# analog.net
KiCad netlist of a schematic drawn in Altium Designer
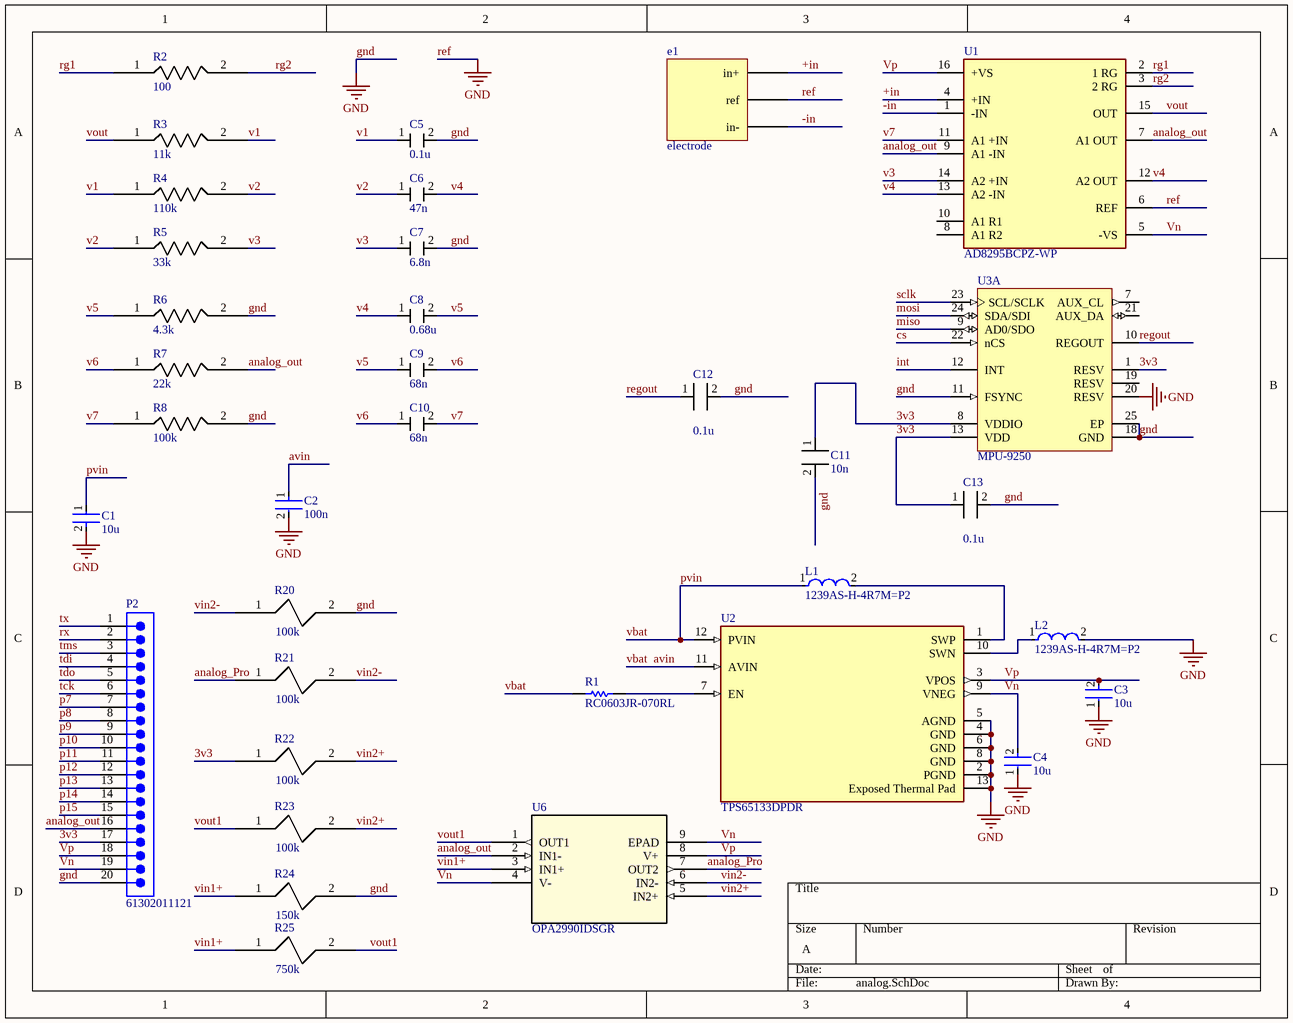
[diagram p0: analog.SchDoc]

(export (version "E")
  (design (tool "Eeschema 10.0.6"))
  (components
    (comp (ref "C1")
      (value "10u")
      (footprint "FP-C1608-080-0_1-MFG")
      (description "C19702")
      (fields (field (name "VOLTAGE") "10V") (field (name "TOLERANCE") "10%"))
      (libsource (lib "Altium Content Vault") (part "236180d848d6139a670b325ea6854c9"))
    )
    (comp (ref "C2")
      (value "100n")
      (footprint "FP-CGA3E-0_3-0_1-IPC_A")
      (description "C14663")
      (fields (field (name "TOLERANCE") "10%") (field (name "VOLTAGE") "50V"))
      (libsource (lib "Altium Content Vault") (part "b4654b650e69147ec39a6b967a45e02"))
    )
    (comp (ref "C3")
      (value "10u")
      (footprint "FP-C1608-080-0_1-MFG")
      (description "C6119842")
      (fields (field (name "VOLTAGE") "10V") (field (name "TOLERANCE") "10%"))
      (libsource (lib "Altium Content Vault") (part "236180d848d6139a670b325ea6854c9"))
    )
    (comp (ref "C4")
      (value "10u")
      (footprint "FP-C1608-080-0_1-MFG")
      (description "C6119842")
      (fields (field (name "VOLTAGE") "10V") (field (name "TOLERANCE") "10%"))
      (libsource (lib "Altium Content Vault") (part "236180d848d6139a670b325ea6854c9"))
    )
    (comp (ref "C5")
      (value "genCap")
      (footprint "GeneralCap")
      (description "C14663")
      (fields (field (name "C") "0.1u"))
      (libsource (lib "") (part "genCap_1"))
    )
    (comp (ref "C6")
      (value "genCap")
      (footprint "GeneralCap")
      (description "C107093")
      (fields (field (name "C") "47n"))
      (libsource (lib "") (part "genCap_1"))
    )
    (comp (ref "C7")
      (value "genCap")
      (footprint "GeneralCap")
      (description "C162241")
      (fields (field (name "C") "6.8n"))
      (libsource (lib "") (part "genCap_1"))
    )
    (comp (ref "C8")
      (value "genCap")
      (footprint "GeneralCap")
      (description "C694504")
      (fields (field (name "C") "0.68u"))
      (libsource (lib "") (part "genCap_1"))
    )
    (comp (ref "C9")
      (value "genCap")
      (footprint "GeneralCap")
      (description "C107098")
      (fields (field (name "C") "68n"))
      (libsource (lib "") (part "genCap_1"))
    )
    (comp (ref "C10")
      (value "genCap")
      (footprint "GeneralCap")
      (description "C107098")
      (fields (field (name "C") "68n"))
      (libsource (lib "") (part "genCap_1"))
    )
    (comp (ref "C11")
      (value "genCap")
      (footprint "GeneralCap")
      (description "C100042")
      (fields (field (name "C") "10n"))
      (libsource (lib "seniorDesign") (part "genCap"))
    )
    (comp (ref "C12")
      (value "genCap")
      (footprint "GeneralCap")
      (description "C14663")
      (fields (field (name "C") "0.1u"))
      (libsource (lib "seniorDesign") (part "genCap"))
    )
    (comp (ref "C13")
      (value "genCap")
      (footprint "GeneralCap")
      (description "C14663")
      (fields (field (name "C") "0.1u"))
      (libsource (lib "seniorDesign") (part "genCap"))
    )
    (comp (ref "e1")
      (value "electrode")
      (footprint "electrode")
      (libsource (lib "sEMG_lib") (part "electrode"))
    )
    (comp (ref "L1")
      (value "1239AS-H-4R7M=P2")
      (footprint "FP-DFE252012C-IPC_A")
      (description "C882976")
      (fields (field (name "TOLERANCE") "20%"))
      (libsource (lib "Altium Content Vault") (part "725321dda6339637d4d059423bc1c3c"))
    )
    (comp (ref "L2")
      (value "1239AS-H-4R7M=P2")
      (footprint "FP-DFE252012C-IPC_A")
      (description "C882976")
      (fields (field (name "TOLERANCE") "20%"))
      (libsource (lib "Altium Content Vault") (part "725321dda6339637d4d059423bc1c3c"))
    )
    (comp (ref "P2")
      (value "61302011121")
      (footprint "61302011121")
      (libsource (lib "Altium Content Vault") (part "Header_Male_1R_20P"))
    )
    (comp (ref "R1")
      (value "RC0603JR-070RL")
      (footprint "RESC1608X55X25ML10T15")
      (description "C95177")
      (fields (field (name "TOLERANCE") "5%") (field (name "MANUFACTURER") "Yageo"))
      (libsource (lib "Altium Content Vault") (part "RES-2"))
    )
    (comp (ref "R2")
      (value "genRes")
      (footprint "GeneralCap")
      (description "C105588")
      (fields (field (name "R") "100"))
      (libsource (lib "seniorDesign") (part "genRes"))
    )
    (comp (ref "R3")
      (value "genRes")
      (footprint "GeneralCap")
      (description "C137801")
      (fields (field (name "R") "11k"))
      (libsource (lib "seniorDesign") (part "genRes"))
    )
    (comp (ref "R4")
      (value "genRes")
      (footprint "GeneralCap")
      (description "C2906984")
      (fields (field (name "R") "110k"))
      (libsource (lib "seniorDesign") (part "genRes"))
    )
    (comp (ref "R5")
      (value "genRes")
      (footprint "GeneralCap")
      (description "C4216")
      (fields (field (name "R") "33k"))
      (libsource (lib "seniorDesign") (part "genRes"))
    )
    (comp (ref "R6")
      (value "genRes")
      (footprint "GeneralCap")
      (description "C2088918")
      (fields (field (name "R") "4.3k"))
      (libsource (lib "seniorDesign") (part "genRes"))
    )
    (comp (ref "R7")
      (value "genRes")
      (footprint "GeneralCap")
      (description "C2907015")
      (fields (field (name "R") "22k"))
      (libsource (lib "seniorDesign") (part "genRes"))
    )
    (comp (ref "R8")
      (value "genRes")
      (footprint "GeneralCap")
      (description "C14675")
      (fields (field (name "R") "100k"))
      (libsource (lib "seniorDesign") (part "genRes"))
    )
    (comp (ref "R20")
      (value "genRes")
      (footprint "GeneralCap")
      (description "C14675")
      (fields (field (name "R") "100k"))
      (libsource (lib "") (part "genRes_1"))
    )
    (comp (ref "R21")
      (value "genRes")
      (footprint "GeneralCap")
      (description "C14675")
      (fields (field (name "R") "100k"))
      (libsource (lib "") (part "genRes_1"))
    )
    (comp (ref "R22")
      (value "genRes")
      (footprint "GeneralCap")
      (description "C14675")
      (fields (field (name "R") "100k"))
      (libsource (lib "") (part "genRes_1"))
    )
    (comp (ref "R23")
      (value "genRes")
      (footprint "GeneralCap")
      (description "C14675")
      (fields (field (name "R") "100k"))
      (libsource (lib "") (part "genRes_1"))
    )
    (comp (ref "R24")
      (value "genRes")
      (footprint "GeneralCap")
      (description "C2906993")
      (fields (field (name "R") "150k"))
      (libsource (lib "") (part "genRes_1"))
    )
    (comp (ref "R25")
      (value "genRes")
      (footprint "GeneralCap")
      (description "C2849084")
      (fields (field (name "R") "750k"))
      (libsource (lib "") (part "genRes_1"))
    )
    (comp (ref "U1")
      (value "AD8295BCPZ-WP")
      (footprint "FP-CP-16-19-IPC_C")
      (description "IC INST AMP 3 CIRCUIT 16LFCSP")
      (libsource (lib "Altium Content Vault") (part "bd0dc2e681ee70e99c4be2d20952a10"))
    )
    (comp (ref "U2")
      (value "TPS65133DPDR")
      (footprint "FP-DPD0012A-MFG")
      (description "C134100")
      (libsource (lib "Altium Content Vault") (part "cb0e1e7d26f86b63177112bdd55f499"))
    )
    (comp (ref "U3")
      (value "MPU-9250")
      (footprint "INSE-QFN-24-1700X1540TP_M")
      (description "9-axis MotionTracking device, 2.4 to 3,6 V, -40 to 85 degC, 24-Pin QFN, RoHS, Tape and Reel")
      (fields (field (name "MANUFACTURER") "InvenSense"))
      (libsource (lib "Altium Content Vault") (part "INSE-MPU-9250-QFN-24"))
    )
    (comp (ref "U6")
      (value "OPA2990IDSGR")
      (footprint "WSON8_DSG_TEX")
      (description "C2057874")
      (libsource (lib "OPA2990IDSGR") (part "OPA2990IDSGR"))
    )
  )
  (nets
    (net (code "1") (name "/+in") (class "Default")
      (node (ref "U1") (pin "4") (pinfunction "+IN_4") (pintype "tri_state"))
      (node (ref "e1") (pin "in+") (pinfunction "in+_in+") (pintype "passive"))
    )
    (net (code "2") (name "/-in") (class "Default")
      (node (ref "U1") (pin "1") (pinfunction "-IN_1") (pintype "tri_state"))
      (node (ref "e1") (pin "in-") (pinfunction "in-_in-") (pintype "passive"))
    )
    (net (code "3") (name "/3v3") (class "Default")
      (node (ref "C11") (pin "1") (pinfunction "1_1") (pintype "passive"))
      (node (ref "C13") (pin "1") (pinfunction "1_1") (pintype "passive"))
      (node (ref "P2") (pin "17") (pinfunction "17_17") (pintype "passive"))
      (node (ref "R22") (pin "1") (pinfunction "1_1") (pintype "passive"))
      (node (ref "U3") (pin "1") (pinfunction "RESV_1") (pintype "power_in"))
      (node (ref "U3") (pin "13") (pinfunction "VDD_13") (pintype "power_in"))
      (node (ref "U3") (pin "8") (pinfunction "VDDIO_8") (pintype "power_in"))
    )
    (net (code "4") (name "/Vn") (class "Default")
      (node (ref "C4") (pin "2") (pinfunction "2_2") (pintype "passive"))
      (node (ref "P2") (pin "19") (pinfunction "19_19") (pintype "passive"))
      (node (ref "U1") (pin "5") (pinfunction "-VS_5") (pintype "power_in"))
      (node (ref "U2") (pin "9") (pinfunction "VNEG_9") (pintype "output"))
      (node (ref "U6") (pin "4") (pinfunction "V-_4") (pintype "power_in"))
      (node (ref "U6") (pin "9") (pinfunction "EPAD_9") (pintype "power_in"))
    )
    (net (code "5") (name "/Vp") (class "Default")
      (node (ref "C3") (pin "2") (pinfunction "2_2") (pintype "passive"))
      (node (ref "P2") (pin "18") (pinfunction "18_18") (pintype "passive"))
      (node (ref "U1") (pin "16") (pinfunction "+VS_16") (pintype "power_in"))
      (node (ref "U2") (pin "3") (pinfunction "VPOS_3") (pintype "output"))
      (node (ref "U6") (pin "8") (pinfunction "V+_8") (pintype "power_in"))
    )
    (net (code "6") (name "/analog_Pro") (class "Default")
      (node (ref "R21") (pin "1") (pinfunction "1_1") (pintype "passive"))
      (node (ref "U6") (pin "7") (pinfunction "OUT2_7") (pintype "output"))
    )
    (net (code "7") (name "/analog_out") (class "Default")
      (node (ref "P2") (pin "16") (pinfunction "16_16") (pintype "passive"))
      (node (ref "R7") (pin "2") (pinfunction "2_2") (pintype "passive"))
      (node (ref "U1") (pin "7") (pinfunction "A1_OUT_7") (pintype "passive"))
      (node (ref "U1") (pin "9") (pinfunction "A1_-IN_9") (pintype "tri_state"))
      (node (ref "U6") (pin "2") (pinfunction "IN1-_2") (pintype "input"))
    )
    (net (code "8") (name "/avin") (class "Default")
      (node (ref "C1") (pin "1") (pinfunction "1_1") (pintype "passive"))
      (node (ref "C2") (pin "1") (pinfunction "1_1") (pintype "passive"))
      (node (ref "L1") (pin "1") (pinfunction "1_1") (pintype "passive"))
      (node (ref "R1") (pin "1") (pinfunction "1_1") (pintype "passive"))
      (node (ref "U2") (pin "11") (pinfunction "AVIN_11") (pintype "input"))
      (node (ref "U2") (pin "12") (pinfunction "PVIN_12") (pintype "input"))
    )
    (net (code "9") (name "/cs") (class "Default")
      (node (ref "U3") (pin "22") (pinfunction "nCS_22") (pintype "input"))
    )
    (net (code "10") (name "/int") (class "Default")
      (node (ref "U3") (pin "12") (pinfunction "INT_12") (pintype "tri_state"))
    )
    (net (code "11") (name "/miso") (class "Default")
      (node (ref "U3") (pin "9") (pinfunction "AD0/SDO_9") (pintype "bidirectional"))
    )
    (net (code "12") (name "/mosi") (class "Default")
      (node (ref "U3") (pin "24") (pinfunction "SDA/SDI_24") (pintype "bidirectional"))
    )
    (net (code "13") (name "/p7") (class "Default")
      (node (ref "P2") (pin "7") (pinfunction "7_7") (pintype "passive"))
    )
    (net (code "14") (name "/p8") (class "Default")
      (node (ref "P2") (pin "8") (pinfunction "8_8") (pintype "passive"))
    )
    (net (code "15") (name "/p9") (class "Default")
      (node (ref "P2") (pin "9") (pinfunction "9_9") (pintype "passive"))
    )
    (net (code "16") (name "/p10") (class "Default")
      (node (ref "P2") (pin "10") (pinfunction "10_10") (pintype "passive"))
    )
    (net (code "17") (name "/p11") (class "Default")
      (node (ref "P2") (pin "11") (pinfunction "11_11") (pintype "passive"))
    )
    (net (code "18") (name "/p12") (class "Default")
      (node (ref "P2") (pin "12") (pinfunction "12_12") (pintype "passive"))
    )
    (net (code "19") (name "/p13") (class "Default")
      (node (ref "P2") (pin "13") (pinfunction "13_13") (pintype "passive"))
    )
    (net (code "20") (name "/p14") (class "Default")
      (node (ref "P2") (pin "14") (pinfunction "14_14") (pintype "passive"))
    )
    (net (code "21") (name "/p15") (class "Default")
      (node (ref "P2") (pin "15") (pinfunction "15_15") (pintype "passive"))
    )
    (net (code "22") (name "/regout") (class "Default")
      (node (ref "C12") (pin "1") (pinfunction "1_1") (pintype "passive"))
      (node (ref "U3") (pin "10") (pinfunction "REGOUT_10") (pintype "passive"))
    )
    (net (code "23") (name "/rg1") (class "Default")
      (node (ref "R2") (pin "1") (pinfunction "1_1") (pintype "passive"))
      (node (ref "U1") (pin "2") (pinfunction "1_RG_2") (pintype "passive"))
    )
    (net (code "24") (name "/rg2") (class "Default")
      (node (ref "R2") (pin "2") (pinfunction "2_2") (pintype "passive"))
      (node (ref "U1") (pin "3") (pinfunction "2_RG_3") (pintype "passive"))
    )
    (net (code "25") (name "/rx") (class "Default")
      (node (ref "P2") (pin "2") (pinfunction "2_2") (pintype "passive"))
    )
    (net (code "26") (name "/sclk") (class "Default")
      (node (ref "U3") (pin "23") (pinfunction "SCL/SCLK_23") (pintype "input"))
    )
    (net (code "27") (name "/tck") (class "Default")
      (node (ref "P2") (pin "6") (pinfunction "6_6") (pintype "passive"))
    )
    (net (code "28") (name "/tdi") (class "Default")
      (node (ref "P2") (pin "4") (pinfunction "4_4") (pintype "passive"))
    )
    (net (code "29") (name "/tdo") (class "Default")
      (node (ref "P2") (pin "5") (pinfunction "5_5") (pintype "passive"))
    )
    (net (code "30") (name "/tms") (class "Default")
      (node (ref "P2") (pin "3") (pinfunction "3_3") (pintype "passive"))
    )
    (net (code "31") (name "/tx") (class "Default")
      (node (ref "P2") (pin "1") (pinfunction "1_1") (pintype "passive"))
    )
    (net (code "32") (name "/v1") (class "Default")
      (node (ref "C5") (pin "1") (pinfunction "1_1") (pintype "passive"))
      (node (ref "R3") (pin "2") (pinfunction "2_2") (pintype "passive"))
      (node (ref "R4") (pin "1") (pinfunction "1_1") (pintype "passive"))
    )
    (net (code "33") (name "/v2") (class "Default")
      (node (ref "C6") (pin "1") (pinfunction "1_1") (pintype "passive"))
      (node (ref "R4") (pin "2") (pinfunction "2_2") (pintype "passive"))
      (node (ref "R5") (pin "1") (pinfunction "1_1") (pintype "passive"))
    )
    (net (code "34") (name "/v3") (class "Default")
      (node (ref "C7") (pin "1") (pinfunction "1_1") (pintype "passive"))
      (node (ref "R5") (pin "2") (pinfunction "2_2") (pintype "passive"))
      (node (ref "U1") (pin "14") (pinfunction "A2_+IN_14") (pintype "tri_state"))
    )
    (net (code "35") (name "/v4") (class "Default")
      (node (ref "C6") (pin "2") (pinfunction "2_2") (pintype "passive"))
      (node (ref "C8") (pin "1") (pinfunction "1_1") (pintype "passive"))
      (node (ref "U1") (pin "12") (pinfunction "A2_OUT_12") (pintype "passive"))
      (node (ref "U1") (pin "13") (pinfunction "A2_-IN_13") (pintype "tri_state"))
    )
    (net (code "36") (name "/v5") (class "Default")
      (node (ref "C8") (pin "2") (pinfunction "2_2") (pintype "passive"))
      (node (ref "C9") (pin "1") (pinfunction "1_1") (pintype "passive"))
      (node (ref "R6") (pin "1") (pinfunction "1_1") (pintype "passive"))
    )
    (net (code "37") (name "/v6") (class "Default")
      (node (ref "C10") (pin "1") (pinfunction "1_1") (pintype "passive"))
      (node (ref "C9") (pin "2") (pinfunction "2_2") (pintype "passive"))
      (node (ref "R7") (pin "1") (pinfunction "1_1") (pintype "passive"))
    )
    (net (code "38") (name "/v7") (class "Default")
      (node (ref "C10") (pin "2") (pinfunction "2_2") (pintype "passive"))
      (node (ref "R8") (pin "1") (pinfunction "1_1") (pintype "passive"))
      (node (ref "U1") (pin "11") (pinfunction "A1_+IN_11") (pintype "tri_state"))
    )
    (net (code "39") (name "/vin1+") (class "Default")
      (node (ref "R24") (pin "1") (pinfunction "1_1") (pintype "passive"))
      (node (ref "R25") (pin "1") (pinfunction "1_1") (pintype "passive"))
      (node (ref "U6") (pin "3") (pinfunction "IN1+_3") (pintype "input"))
    )
    (net (code "40") (name "/vin2+") (class "Default")
      (node (ref "R22") (pin "2") (pinfunction "2_2") (pintype "passive"))
      (node (ref "R23") (pin "2") (pinfunction "2_2") (pintype "passive"))
      (node (ref "U6") (pin "5") (pinfunction "IN2+_5") (pintype "input"))
    )
    (net (code "41") (name "/vin2-") (class "Default")
      (node (ref "R20") (pin "1") (pinfunction "1_1") (pintype "passive"))
      (node (ref "R21") (pin "2") (pinfunction "2_2") (pintype "passive"))
      (node (ref "U6") (pin "6") (pinfunction "IN2-_6") (pintype "input"))
    )
    (net (code "42") (name "/vout") (class "Default")
      (node (ref "R3") (pin "1") (pinfunction "1_1") (pintype "passive"))
      (node (ref "U1") (pin "15") (pinfunction "OUT_15") (pintype "passive"))
    )
    (net (code "43") (name "/vout1") (class "Default")
      (node (ref "R23") (pin "1") (pinfunction "1_1") (pintype "passive"))
      (node (ref "R25") (pin "2") (pinfunction "2_2") (pintype "passive"))
      (node (ref "U6") (pin "1") (pinfunction "OUT1_1") (pintype "output"))
    )
    (net (code "44") (name "GND") (class "Default")
      (node (ref "C1") (pin "2") (pinfunction "2_2") (pintype "passive"))
      (node (ref "C11") (pin "2") (pinfunction "2_2") (pintype "passive"))
      (node (ref "C12") (pin "2") (pinfunction "2_2") (pintype "passive"))
      (node (ref "C13") (pin "2") (pinfunction "2_2") (pintype "passive"))
      (node (ref "C2") (pin "2") (pinfunction "2_2") (pintype "passive"))
      (node (ref "C3") (pin "1") (pinfunction "1_1") (pintype "passive"))
      (node (ref "C4") (pin "1") (pinfunction "1_1") (pintype "passive"))
      (node (ref "C5") (pin "2") (pinfunction "2_2") (pintype "passive"))
      (node (ref "C7") (pin "2") (pinfunction "2_2") (pintype "passive"))
      (node (ref "L2") (pin "2") (pinfunction "2_2") (pintype "passive"))
      (node (ref "P2") (pin "20") (pinfunction "20_20") (pintype "passive"))
      (node (ref "R20") (pin "2") (pinfunction "2_2") (pintype "passive"))
      (node (ref "R24") (pin "2") (pinfunction "2_2") (pintype "passive"))
      (node (ref "R6") (pin "2") (pinfunction "2_2") (pintype "passive"))
      (node (ref "R8") (pin "2") (pinfunction "2_2") (pintype "passive"))
      (node (ref "U1") (pin "6") (pinfunction "REF_6") (pintype "passive"))
      (node (ref "U2") (pin "13") (pinfunction "Exposed_Thermal_Pad_13") (pintype "power_in"))
      (node (ref "U2") (pin "2") (pinfunction "PGND_2") (pintype "power_in"))
      (node (ref "U2") (pin "4") (pinfunction "GND_4") (pintype "power_in"))
      (node (ref "U2") (pin "5") (pinfunction "AGND_5") (pintype "power_in"))
      (node (ref "U2") (pin "6") (pinfunction "GND_6") (pintype "power_in"))
      (node (ref "U2") (pin "8") (pinfunction "GND_8") (pintype "power_in"))
      (node (ref "U3") (pin "11") (pinfunction "FSYNC_11") (pintype "input"))
      (node (ref "U3") (pin "18") (pinfunction "GND_18") (pintype "power_in"))
      (node (ref "U3") (pin "20") (pinfunction "RESV_20") (pintype "power_in"))
      (node (ref "U3") (pin "25") (pinfunction "EP_25") (pintype "passive"))
      (node (ref "e1") (pin "ref") (pinfunction "ref_ref") (pintype "passive"))
    )
    (net (code "45") (name "Net-(U2-EN)") (class "Default")
      (node (ref "R1") (pin "2") (pinfunction "2_2") (pintype "passive"))
      (node (ref "U2") (pin "7") (pinfunction "EN_7") (pintype "input"))
    )
    (net (code "46") (name "Net-(U2-SWN)") (class "Default")
      (node (ref "L2") (pin "1") (pinfunction "1_1") (pintype "passive"))
      (node (ref "U2") (pin "10") (pinfunction "SWN_10") (pintype "power_in"))
    )
    (net (code "47") (name "Net-(U2-SWP)") (class "Default")
      (node (ref "L1") (pin "2") (pinfunction "2_2") (pintype "passive"))
      (node (ref "U2") (pin "1") (pinfunction "SWP_1") (pintype "power_in"))
    )
    (net (code "48") (name "unconnected-(U1-A1_R1-Pad10)") (class "Default")
      (node (ref "U1") (pin "10") (pinfunction "A1_R1_10") (pintype "passive"))
    )
    (net (code "49") (name "unconnected-(U1-A1_R2-Pad8)") (class "Default")
      (node (ref "U1") (pin "8") (pinfunction "A1_R2_8") (pintype "passive"))
    )
    (net (code "50") (name "unconnected-(U3A-AUX_CL-Pad7)") (class "Default")
      (node (ref "U3") (pin "7") (pinfunction "AUX_CL_7") (pintype "output"))
    )
    (net (code "51") (name "unconnected-(U3A-AUX_DA-Pad21)") (class "Default")
      (node (ref "U3") (pin "21") (pinfunction "AUX_DA_21") (pintype "bidirectional"))
    )
    (net (code "52") (name "unconnected-(U3A-RESV-Pad19)") (class "Default")
      (node (ref "U3") (pin "19") (pinfunction "RESV_19") (pintype "passive"))
    )
  )
)
